# pcb-breakout-pan1740.net
KiCad netlist of a schematic drawn in EAGLE
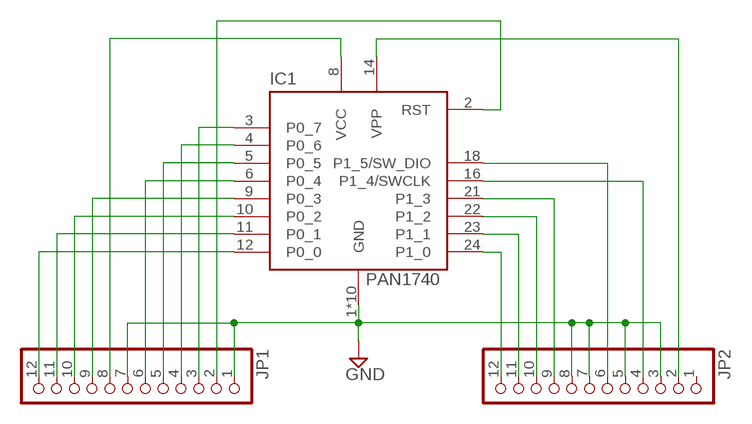
[diagram p0: schematic, sheet 1]

(export (version "E")
  (design (tool "Eeschema 10.0.6"))
  (components
    (comp (ref "IC1")
      (value "PAN1740")
      (footprint "eagle-import:PAN1740")
      (libsource (lib "eagle-import") (part "PAN1740"))
    )
    (comp (ref "JP1")
      (value "PINHD-1X12")
      (footprint "eagle-import:1X12")
      (libsource (lib "eagle-import") (part "PINHD-1X12"))
    )
    (comp (ref "JP2")
      (value "PINHD-1X12")
      (footprint "eagle-import:1X12")
      (libsource (lib "eagle-import") (part "PINHD-1X12"))
    )
  )
  (nets
    (net (code "1") (name "GND") (class "Default")
      (node (ref "IC1") (pin "1") (pinfunction "GND_1") (pintype "power_in"))
      (node (ref "IC1") (pin "15") (pinfunction "GND_15") (pintype "power_in"))
      (node (ref "IC1") (pin "17") (pinfunction "GND_17") (pintype "power_in"))
      (node (ref "IC1") (pin "19") (pinfunction "GND_19") (pintype "power_in"))
      (node (ref "IC1") (pin "20") (pinfunction "GND_20") (pintype "power_in"))
      (node (ref "IC1") (pin "7") (pinfunction "GND_7") (pintype "power_in"))
      (node (ref "IC1") (pin "A") (pinfunction "GND_A") (pintype "power_in"))
      (node (ref "IC1") (pin "B") (pinfunction "GND_B") (pintype "power_in"))
      (node (ref "IC1") (pin "C") (pinfunction "GND_C") (pintype "power_in"))
      (node (ref "IC1") (pin "D") (pinfunction "GND_D") (pintype "power_in"))
      (node (ref "JP1") (pin "1") (pinfunction "1_1") (pintype "passive"))
      (node (ref "JP1") (pin "7") (pinfunction "7_7") (pintype "passive"))
      (node (ref "JP2") (pin "3") (pinfunction "3_3") (pintype "passive"))
      (node (ref "JP2") (pin "5") (pinfunction "5_5") (pintype "passive"))
      (node (ref "JP2") (pin "7") (pinfunction "7_7") (pintype "passive"))
      (node (ref "JP2") (pin "8") (pinfunction "8_8") (pintype "passive"))
    )
    (net (code "2") (name "Net-(IC1-P0_0)") (class "Default")
      (node (ref "IC1") (pin "12") (pinfunction "P0_0_12") (pintype "bidirectional"))
      (node (ref "JP1") (pin "12") (pinfunction "12_12") (pintype "passive"))
    )
    (net (code "3") (name "Net-(IC1-P0_1)") (class "Default")
      (node (ref "IC1") (pin "11") (pinfunction "P0_1_11") (pintype "bidirectional"))
      (node (ref "JP1") (pin "11") (pinfunction "11_11") (pintype "passive"))
    )
    (net (code "4") (name "Net-(IC1-P0_2)") (class "Default")
      (node (ref "IC1") (pin "10") (pinfunction "P0_2_10") (pintype "bidirectional"))
      (node (ref "JP1") (pin "10") (pinfunction "10_10") (pintype "passive"))
    )
    (net (code "5") (name "Net-(IC1-P0_3)") (class "Default")
      (node (ref "IC1") (pin "9") (pinfunction "P0_3_9") (pintype "bidirectional"))
      (node (ref "JP1") (pin "9") (pinfunction "9_9") (pintype "passive"))
    )
    (net (code "6") (name "Net-(IC1-P0_4)") (class "Default")
      (node (ref "IC1") (pin "6") (pinfunction "P0_4_6") (pintype "bidirectional"))
      (node (ref "JP1") (pin "6") (pinfunction "6_6") (pintype "passive"))
    )
    (net (code "7") (name "Net-(IC1-P0_5)") (class "Default")
      (node (ref "IC1") (pin "5") (pinfunction "P0_5_5") (pintype "bidirectional"))
      (node (ref "JP1") (pin "5") (pinfunction "5_5") (pintype "passive"))
    )
    (net (code "8") (name "Net-(IC1-P0_6)") (class "Default")
      (node (ref "IC1") (pin "4") (pinfunction "P0_6_4") (pintype "bidirectional"))
      (node (ref "JP1") (pin "4") (pinfunction "4_4") (pintype "passive"))
    )
    (net (code "9") (name "Net-(IC1-P0_7)") (class "Default")
      (node (ref "IC1") (pin "3") (pinfunction "P0_7_3") (pintype "bidirectional"))
      (node (ref "JP1") (pin "3") (pinfunction "3_3") (pintype "passive"))
    )
    (net (code "10") (name "Net-(IC1-P1_0)") (class "Default")
      (node (ref "IC1") (pin "24") (pinfunction "P1_0_24") (pintype "bidirectional"))
      (node (ref "JP2") (pin "12") (pinfunction "12_12") (pintype "passive"))
    )
    (net (code "11") (name "Net-(IC1-P1_1)") (class "Default")
      (node (ref "IC1") (pin "23") (pinfunction "P1_1_23") (pintype "bidirectional"))
      (node (ref "JP2") (pin "11") (pinfunction "11_11") (pintype "passive"))
    )
    (net (code "12") (name "Net-(IC1-P1_2)") (class "Default")
      (node (ref "IC1") (pin "22") (pinfunction "P1_2_22") (pintype "bidirectional"))
      (node (ref "JP2") (pin "10") (pinfunction "10_10") (pintype "passive"))
    )
    (net (code "13") (name "Net-(IC1-P1_3)") (class "Default")
      (node (ref "IC1") (pin "21") (pinfunction "P1_3_21") (pintype "bidirectional"))
      (node (ref "JP2") (pin "9") (pinfunction "9_9") (pintype "passive"))
    )
    (net (code "14") (name "Net-(IC1-P1_4{slash}SWCLK)") (class "Default")
      (node (ref "IC1") (pin "16") (pinfunction "P1_4/SWCLK_16") (pintype "bidirectional"))
      (node (ref "JP2") (pin "4") (pinfunction "4_4") (pintype "passive"))
    )
    (net (code "15") (name "Net-(IC1-P1_5{slash}SW_DIO)") (class "Default")
      (node (ref "IC1") (pin "18") (pinfunction "P1_5/SW_DIO_18") (pintype "bidirectional"))
      (node (ref "JP2") (pin "6") (pinfunction "6_6") (pintype "passive"))
    )
    (net (code "16") (name "Net-(IC1-RST)") (class "Default")
      (node (ref "IC1") (pin "2") (pinfunction "RST_2") (pintype "bidirectional"))
      (node (ref "JP1") (pin "2") (pinfunction "2_2") (pintype "passive"))
    )
    (net (code "17") (name "Net-(IC1-VCC)") (class "Default")
      (node (ref "IC1") (pin "8") (pinfunction "VCC_8") (pintype "bidirectional"))
      (node (ref "JP1") (pin "8") (pinfunction "8_8") (pintype "passive"))
    )
    (net (code "18") (name "Net-(IC1-VPP)") (class "Default")
      (node (ref "IC1") (pin "14") (pinfunction "VPP_14") (pintype "power_in"))
      (node (ref "JP2") (pin "2") (pinfunction "2_2") (pintype "passive"))
    )
    (net (code "19") (name "unconnected-(JP2-Pad1)") (class "Default")
      (node (ref "JP2") (pin "1") (pinfunction "1_1") (pintype "passive"))
    )
  )
)
